# ver1_0.net
KiCad netlist of a schematic drawn in EAGLE
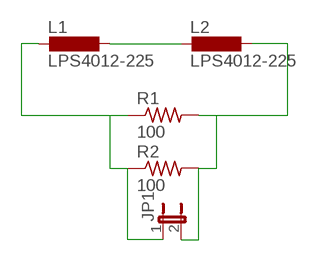
[diagram p0: schematic, sheet 1]

(export (version "E")
  (design (tool "Eeschema 10.0.6"))
  (components
    (comp (ref "JP1")
      (value "JP1E")
      (footprint "eagle-import:JP1")
      (libsource (lib "eagle-import") (part "JP1E"))
    )
    (comp (ref "L1")
      (value "LPS4012-225")
      (footprint "eagle-import:MSS7341")
      (libsource (lib "eagle-import") (part "MSS7341"))
    )
    (comp (ref "L2")
      (value "LPS4012-225")
      (footprint "eagle-import:MSS7341")
      (libsource (lib "eagle-import") (part "MSS7341"))
    )
    (comp (ref "R1")
      (value "100")
      (footprint "eagle-import:R0603")
      (libsource (lib "eagle-import") (part "R-US_R0603"))
    )
    (comp (ref "R2")
      (value "100")
      (footprint "eagle-import:R0603")
      (libsource (lib "eagle-import") (part "R-US_R0603"))
    )
  )
  (nets
    (net (code "1") (name "Net-(L1-1)") (class "Default")
      (node (ref "JP1") (pin "1") (pinfunction "1_1") (pintype "passive"))
      (node (ref "L1") (pin "P$1") (pinfunction "1_P$1") (pintype "passive"))
      (node (ref "R1") (pin "1") (pinfunction "1_1") (pintype "passive"))
      (node (ref "R2") (pin "1") (pinfunction "1_1") (pintype "passive"))
    )
    (net (code "2") (name "Net-(L1-2)") (class "Default")
      (node (ref "L1") (pin "P$2") (pinfunction "2_P$2") (pintype "passive"))
      (node (ref "L2") (pin "P$1") (pinfunction "1_P$1") (pintype "passive"))
    )
    (net (code "3") (name "Net-(L2-2)") (class "Default")
      (node (ref "JP1") (pin "2") (pinfunction "2_2") (pintype "passive"))
      (node (ref "L2") (pin "P$2") (pinfunction "2_P$2") (pintype "passive"))
      (node (ref "R1") (pin "2") (pinfunction "2_2") (pintype "passive"))
      (node (ref "R2") (pin "2") (pinfunction "2_2") (pintype "passive"))
    )
  )
)
